# Power_supply.net
KiCad netlist of a schematic drawn in Altium Designer
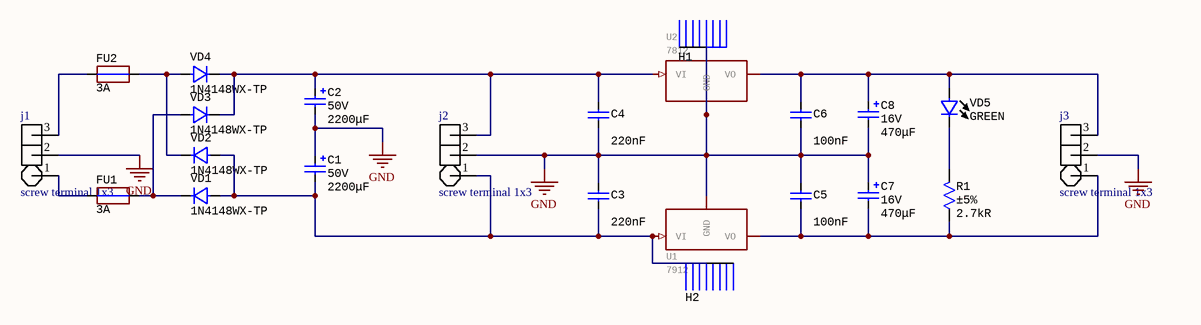
[diagram p0: Power supply.SchDoc]

(export (version "E")
  (design (tool "Eeschema 10.0.6"))
  (components
    (comp (ref "C1")
      (value "2200μF")
      (footprint "CAP Electrolytic TH D16C7.5H31.5")
      (fields
        (field (name "MANUFACTURER") "Wurth")
        (field (name "PARTNUMBER") "860080475013")
        (field (name "VALUEMANUFACTURERPARTNUMBER") "Aluminium capacitor, 2200μF, 50V, ±20%, 54mOhm, 14x10x5 mm, -55...+105°C")
        (field (name "VOLTAGE") "50V")
      )
      (libsource (lib "Passive") (part "Capacitor Aluminium"))
    )
    (comp (ref "C2")
      (value "2200μF")
      (footprint "CAP Electrolytic TH D16C7.5H31.5")
      (fields
        (field (name "MANUFACTURER") "Wurth")
        (field (name "PARTNUMBER") "860080475013")
        (field (name "VALUEMANUFACTURERPARTNUMBER") "Aluminium capacitor, 2200μF, 50V, ±20%, 54mOhm, 14x10x5 mm, -55...+105°C")
        (field (name "VOLTAGE") "50V")
      )
      (libsource (lib "Passive") (part "Capacitor Aluminium"))
    )
    (comp (ref "C3")
      (value "220nF")
      (footprint "CAP Ceramic TH AY2102M29Y5US63L7")
      (fields
        (field (name "MANUFACTURER") "Epcos")
        (field (name "PARTNUMBER") "B32774D4106K000")
        (field (name "VALUEMANUFACTURERPARTNUMBER") "Film capacitor, 220nF, 450VDC, ±10%, 10.9mOhm, 31.5x15 mm, -40...+105°C")
      )
      (libsource (lib "Passive") (part "Capacitor Film"))
    )
    (comp (ref "C4")
      (value "220nF")
      (footprint "CAP Ceramic TH AY2102M29Y5US63L7")
      (fields
        (field (name "MANUFACTURER") "Epcos")
        (field (name "PARTNUMBER") "B32774D4106K000")
        (field (name "VALUEMANUFACTURERPARTNUMBER") "Film capacitor, 220nF, 450VDC, ±10%, 10.9mOhm, 31.5x15 mm, -40...+105°C")
      )
      (libsource (lib "Passive") (part "Capacitor Film"))
    )
    (comp (ref "C5")
      (value "100nF")
      (footprint "CAP Ceramic TH AY2102M29Y5US63L7")
      (fields
        (field (name "MANUFACTURER") "Epcos")
        (field (name "PARTNUMBER") "B32774D4106K000")
        (field (name "VALUEMANUFACTURERPARTNUMBER") "Film capacitor, 100nF, 450VDC, ±10%, 10.9mOhm, 31.5x15 mm, -40...+105°C")
      )
      (libsource (lib "Passive") (part "Capacitor Film"))
    )
    (comp (ref "C6")
      (value "100nF")
      (footprint "CAP Ceramic TH AY2102M29Y5US63L7")
      (fields
        (field (name "MANUFACTURER") "Epcos")
        (field (name "PARTNUMBER") "B32774D4106K000")
        (field (name "VALUEMANUFACTURERPARTNUMBER") "Film capacitor, 100nF, 450VDC, ±10%, 10.9mOhm, 31.5x15 mm, -40...+105°C")
      )
      (libsource (lib "Passive") (part "Capacitor Film"))
    )
    (comp (ref "C7")
      (value "470μF")
      (footprint "CAP Electrolytic TH D10C5H12.5")
      (fields
        (field (name "MANUFACTURER") "Wurth")
        (field (name "PARTNUMBER") "860080475013")
        (field (name "VALUEMANUFACTURERPARTNUMBER") "Aluminium capacitor, 470μF, 16V, ±20%, 54mOhm, 14x10x5 mm, -55...+105°C")
        (field (name "VOLTAGE") "16V")
      )
      (libsource (lib "Passive") (part "Capacitor Aluminium"))
    )
    (comp (ref "C8")
      (value "470μF")
      (footprint "CAP Electrolytic TH D10C5H12.5")
      (fields
        (field (name "MANUFACTURER") "Wurth")
        (field (name "PARTNUMBER") "860080475013")
        (field (name "VALUEMANUFACTURERPARTNUMBER") "Aluminium capacitor, 470μF, 16V, ±20%, 54mOhm, 14x10x5 mm, -55...+105°C")
        (field (name "VOLTAGE") "16V")
      )
      (libsource (lib "Passive") (part "Capacitor Aluminium"))
    )
    (comp (ref "FU1")
      (value "~")
      (footprint "FUSE TH BLX-A")
      (fields
        (field (name "MANUFACTURER") "Littelfuse")
        (field (name "VALUEMANUFACTURERPARTNUMBER") "Electromechanics relay, 250VAC, 3A, 5x20mm, ")
        (field (name "PARTNUMBER") "01110501Z")
        (field (name "MAXCURRENT") "3A")
      )
      (libsource (lib "Fuse") (part "Fuse"))
    )
    (comp (ref "FU2")
      (value "~")
      (footprint "FUSE TH BLX-A")
      (fields
        (field (name "MANUFACTURER") "Littelfuse")
        (field (name "VALUEMANUFACTURERPARTNUMBER") "Electromechanics relay, 250VAC, 3A, 5x20mm, ")
        (field (name "PARTNUMBER") "01110501Z")
        (field (name "MAXCURRENT") "3A")
      )
      (libsource (lib "Fuse") (part "Fuse"))
    )
    (comp (ref "H1")
      (value "Heatsink 1 pad transistor TO220")
      (footprint "Heatsink 1 pad SK95-2M3")
      (libsource (lib "Heatsinks") (part "Heatsink 1 pad transistor TO220"))
    )
    (comp (ref "H2")
      (value "Heatsink 1 pad transistor TO220")
      (footprint "Heatsink 1 pad SK95-2M3")
      (libsource (lib "Heatsinks") (part "Heatsink 1 pad transistor TO220"))
    )
    (comp (ref "j1")
      (value "screw terminal 1x3")
      (footprint "screw terminal 1x3")
      (description "PCB Terminal Block 3 Poles, 5 mm Pitch, 691101710003, Würth Elektronik")
      (fields
        (field (name "MANUFACTURER") "Wurth Electronics")
        (field (name "MANUFACTURER PART NUMBER") "691101710003")
      )
      (libsource (lib "connectors") (part "screw terminal 1x3"))
    )
    (comp (ref "j2")
      (value "screw terminal 1x3")
      (footprint "screw terminal 1x3")
      (description "PCB Terminal Block 3 Poles, 5 mm Pitch, 691101710003, Würth Elektronik")
      (fields
        (field (name "MANUFACTURER") "Wurth Electronics")
        (field (name "MANUFACTURER PART NUMBER") "691101710003")
      )
      (libsource (lib "connectors") (part "screw terminal 1x3"))
    )
    (comp (ref "j3")
      (value "screw terminal 1x3")
      (footprint "screw terminal 1x3")
      (description "PCB Terminal Block 3 Poles, 5 mm Pitch, 691101710003, Würth Elektronik")
      (fields
        (field (name "MANUFACTURER") "Wurth Electronics")
        (field (name "MANUFACTURER PART NUMBER") "691101710003")
      )
      (libsource (lib "connectors") (part "screw terminal 1x3"))
    )
    (comp (ref "R1")
      (value "2.7kR")
      (footprint "RES TH 0.25W H 0207$10")
      (fields
        (field (name "MANUFACTURER") "Yageo")
        (field (name "PARTNUMBER") "RC0201JR-07100RL")
        (field (name "VALUEMANUFACTURERPARTNUMBER") "Resistor film, 2.7kR, ±5%, 0201, 0.25W, -55...+125°C")
        (field (name "TOLERANCE") "±5%")
      )
      (libsource (lib "Passive") (part "Resistor Fixed"))
    )
    (comp (ref "U1")
      (value "7912")
      (footprint "Linear reagulator TH TO220V")
      (description "Negative VOLTAGE REGULATOR")
      (libsource (lib "Linear regulator") (part "79XX"))
    )
    (comp (ref "U2")
      (value "7812")
      (footprint "Linear reagulator TH TO220V")
      (description "Positive VOLTAGE REGULATOR")
      (libsource (lib "Linear regulator") (part "78XX"))
    )
    (comp (ref "VD1")
      (value "~")
      (footprint "Diode TH DO-41 (h) (1n4007)")
      (fields
        (field (name "MANUFACTURER") "Micro Commercial")
        (field (name "VALUEMANUFACTURERPARTNUMBER") "Single diode, 75V, 150mA, 1V, 4ns, SOD-323, -55...+150°C")
        (field (name "VOLTAGE") "75V")
        (field (name "PARTNUMBER") "1N4148WX-TP")
      )
      (libsource (lib "diode") (part "Diode single"))
    )
    (comp (ref "VD2")
      (value "~")
      (footprint "Diode TH DO-41 (h) (1n4007)")
      (fields
        (field (name "MANUFACTURER") "Micro Commercial")
        (field (name "VALUEMANUFACTURERPARTNUMBER") "Single diode, 75V, 150mA, 1V, 4ns, SOD-323, -55...+150°C")
        (field (name "VOLTAGE") "75V")
        (field (name "PARTNUMBER") "1N4148WX-TP")
      )
      (libsource (lib "diode") (part "Diode single"))
    )
    (comp (ref "VD3")
      (value "~")
      (footprint "Diode TH DO-41 (h) (1n4007)")
      (fields
        (field (name "MANUFACTURER") "Micro Commercial")
        (field (name "VALUEMANUFACTURERPARTNUMBER") "Single diode, 75V, 150mA, 1V, 4ns, SOD-323, -55...+150°C")
        (field (name "VOLTAGE") "75V")
        (field (name "PARTNUMBER") "1N4148WX-TP")
      )
      (libsource (lib "diode") (part "Diode single"))
    )
    (comp (ref "VD4")
      (value "~")
      (footprint "Diode TH DO-41 (h) (1n4007)")
      (fields
        (field (name "MANUFACTURER") "Micro Commercial")
        (field (name "VALUEMANUFACTURERPARTNUMBER") "Single diode, 75V, 150mA, 1V, 4ns, SOD-323, -55...+150°C")
        (field (name "VOLTAGE") "75V")
        (field (name "PARTNUMBER") "1N4148WX-TP")
      )
      (libsource (lib "diode") (part "Diode single"))
    )
    (comp (ref "VD5")
      (value "~")
      (footprint "LED TH 5MM")
      (fields
        (field (name "VALUEMANUFACTURERPARTNUMBER") "LED, Green, *, *, *, -55...+150°C")
        (field (name "COLOR") "GREEN")
      )
      (libsource (lib "diode") (part "LED single"))
    )
  )
  (nets
    (net (code "1") (name "GND") (class "Default")
      (node (ref "C1") (pin "1") (pinfunction "1_1") (pintype "passive"))
      (node (ref "C2") (pin "2") (pinfunction "2_2") (pintype "passive"))
      (node (ref "C3") (pin "1") (pinfunction "1_1") (pintype "passive"))
      (node (ref "C4") (pin "2") (pinfunction "2_2") (pintype "passive"))
      (node (ref "C5") (pin "1") (pinfunction "1_1") (pintype "passive"))
      (node (ref "C6") (pin "2") (pinfunction "2_2") (pintype "passive"))
      (node (ref "C7") (pin "1") (pinfunction "1_1") (pintype "passive"))
      (node (ref "C8") (pin "2") (pinfunction "2_2") (pintype "passive"))
      (node (ref "H1") (pin "1") (pinfunction "S_1") (pintype "passive"))
      (node (ref "U1") (pin "1") (pinfunction "GND_1") (pintype "passive"))
      (node (ref "U2") (pin "2") (pinfunction "GND_2") (pintype "passive"))
      (node (ref "j1") (pin "2") (pinfunction "2_2") (pintype "passive"))
      (node (ref "j2") (pin "2") (pinfunction "2_2") (pintype "passive"))
      (node (ref "j3") (pin "2") (pinfunction "2_2") (pintype "passive"))
    )
    (net (code "2") (name "Net-(FU1-Pad1)") (class "Default")
      (node (ref "FU1") (pin "1") (pinfunction "1_1") (pintype "passive"))
      (node (ref "j1") (pin "1") (pinfunction "1_1") (pintype "passive"))
    )
    (net (code "3") (name "Net-(FU1-Pad2)") (class "Default")
      (node (ref "FU1") (pin "2") (pinfunction "2_2") (pintype "passive"))
      (node (ref "VD1") (pin "2") (pinfunction "2_2") (pintype "passive"))
      (node (ref "VD3") (pin "1") (pinfunction "1_1") (pintype "passive"))
    )
    (net (code "4") (name "Net-(FU2-Pad1)") (class "Default")
      (node (ref "FU2") (pin "1") (pinfunction "1_1") (pintype "passive"))
      (node (ref "j1") (pin "3") (pinfunction "3_3") (pintype "passive"))
    )
    (net (code "5") (name "Net-(FU2-Pad2)") (class "Default")
      (node (ref "FU2") (pin "2") (pinfunction "2_2") (pintype "passive"))
      (node (ref "VD2") (pin "2") (pinfunction "2_2") (pintype "passive"))
      (node (ref "VD4") (pin "1") (pinfunction "1_1") (pintype "passive"))
    )
    (net (code "6") (name "Net-(H2-S)") (class "Default")
      (node (ref "C1") (pin "2") (pinfunction "2_2") (pintype "passive"))
      (node (ref "C3") (pin "2") (pinfunction "2_2") (pintype "passive"))
      (node (ref "H2") (pin "1") (pinfunction "S_1") (pintype "passive"))
      (node (ref "U1") (pin "2") (pinfunction "VI_2") (pintype "input"))
      (node (ref "VD1") (pin "1") (pinfunction "1_1") (pintype "passive"))
      (node (ref "VD2") (pin "1") (pinfunction "1_1") (pintype "passive"))
      (node (ref "j2") (pin "1") (pinfunction "1_1") (pintype "passive"))
    )
    (net (code "7") (name "Net-(R1-Pad2)") (class "Default")
      (node (ref "R1") (pin "2") (pinfunction "2_2") (pintype "passive"))
      (node (ref "VD5") (pin "2") (pinfunction "2_2") (pintype "passive"))
    )
    (net (code "8") (name "Net-(U1-VO)") (class "Default")
      (node (ref "C5") (pin "2") (pinfunction "2_2") (pintype "passive"))
      (node (ref "C7") (pin "2") (pinfunction "2_2") (pintype "passive"))
      (node (ref "R1") (pin "1") (pinfunction "1_1") (pintype "passive"))
      (node (ref "U1") (pin "3") (pinfunction "VO_3") (pintype "passive"))
      (node (ref "j3") (pin "1") (pinfunction "1_1") (pintype "passive"))
    )
    (net (code "9") (name "Net-(U2-VI)") (class "Default")
      (node (ref "C2") (pin "1") (pinfunction "1_1") (pintype "passive"))
      (node (ref "C4") (pin "1") (pinfunction "1_1") (pintype "passive"))
      (node (ref "U2") (pin "1") (pinfunction "VI_1") (pintype "input"))
      (node (ref "VD3") (pin "2") (pinfunction "2_2") (pintype "passive"))
      (node (ref "VD4") (pin "2") (pinfunction "2_2") (pintype "passive"))
      (node (ref "j2") (pin "3") (pinfunction "3_3") (pintype "passive"))
    )
    (net (code "10") (name "Net-(U2-VO)") (class "Default")
      (node (ref "C6") (pin "1") (pinfunction "1_1") (pintype "passive"))
      (node (ref "C8") (pin "1") (pinfunction "1_1") (pintype "passive"))
      (node (ref "U2") (pin "3") (pinfunction "VO_3") (pintype "passive"))
      (node (ref "VD5") (pin "1") (pinfunction "1_1") (pintype "passive"))
      (node (ref "j3") (pin "3") (pinfunction "3_3") (pintype "passive"))
    )
  )
)
